# emonTx4-PiZero.net
KiCad netlist of a schematic drawn in EAGLE
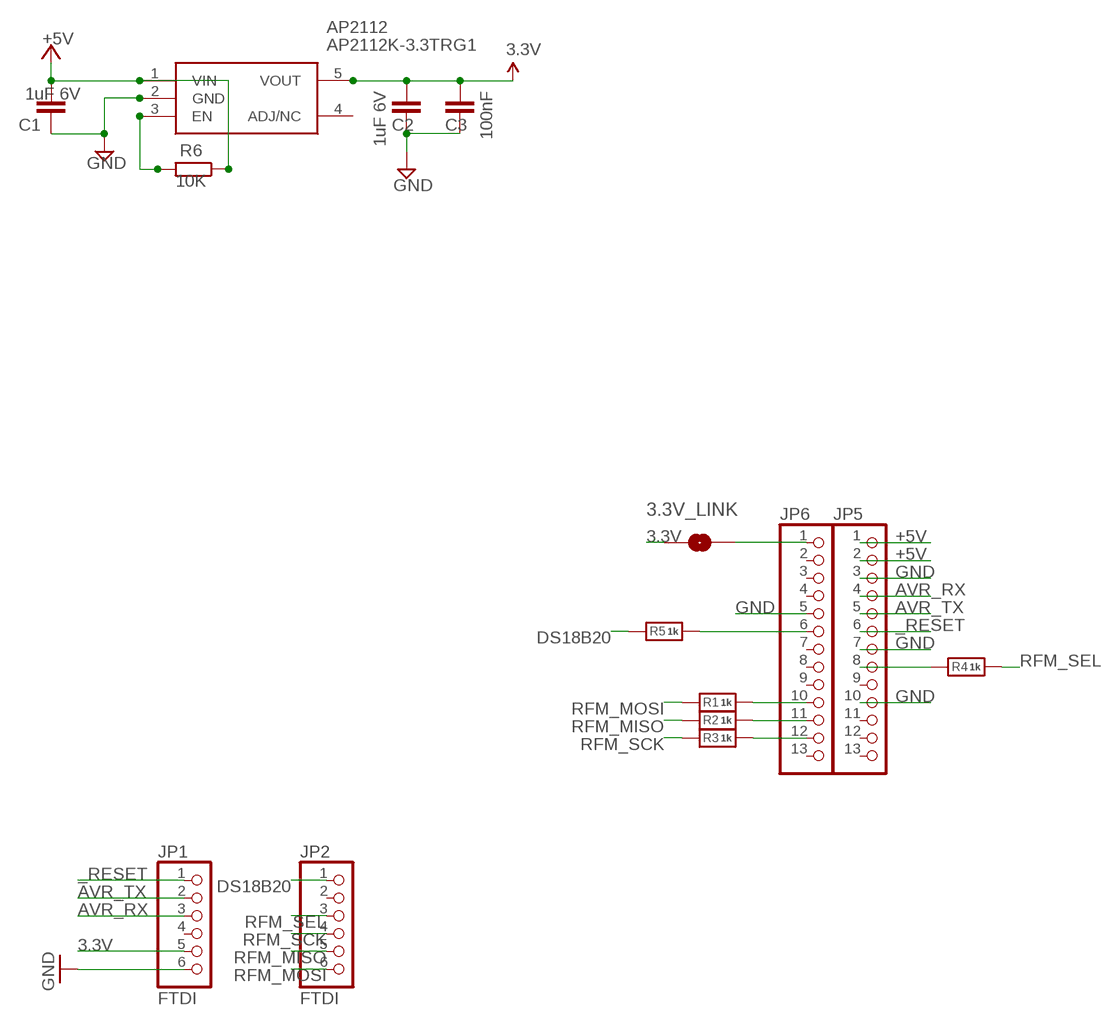
[diagram p0: schematic, sheet 1]

(export (version "E")
  (design (tool "Eeschema 10.0.6"))
  (components
    (comp (ref "3.3V_LINK")
      (value "SOLDERJUMPERNC")
      (footprint "eagle-import:SJ_2S")
      (libsource (lib "eagle-import") (part "SOLDERJUMPERNC"))
    )
    (comp (ref "AP2112")
      (value "AP2112K-3.3TRG1")
      (footprint "eagle-import:SOT95P282X130-5N")
      (fields (field (name "MOUSER_PART_NUMBER") "621-AP2112K-3.3TRG1"))
      (libsource (lib "eagle-import") (part "AP2112K-3.3TRG1"))
    )
    (comp (ref "C1")
      (value "1uF 6V")
      (footprint "eagle-import:C0603")
      (libsource (lib "eagle-import") (part "C-EUC0603"))
    )
    (comp (ref "C2")
      (value "1uF 6V")
      (footprint "eagle-import:C0603")
      (libsource (lib "eagle-import") (part "C-EUC0603"))
    )
    (comp (ref "C3")
      (value "100nF")
      (footprint "eagle-import:C0603")
      (libsource (lib "eagle-import") (part "C-EUC0603"))
    )
    (comp (ref "JP1")
      (value "FTDI")
      (footprint "eagle-import:1X06_ROUND_70")
      (libsource (lib "eagle-import") (part "HEADER-1X670MIL"))
    )
    (comp (ref "JP2")
      (value "FTDI")
      (footprint "eagle-import:1X06_ROUND_70")
      (libsource (lib "eagle-import") (part "HEADER-1X670MIL"))
    )
    (comp (ref "JP5")
      (value "PINHD-1X13_BIG")
      (footprint "eagle-import:1X13-BIG")
      (libsource (lib "eagle-import") (part "PINHD-1X13_BIG"))
    )
    (comp (ref "JP6")
      (value "PINHD-1X13_BIG")
      (footprint "eagle-import:1X13-BIG")
      (libsource (lib "eagle-import") (part "PINHD-1X13_BIG"))
    )
    (comp (ref "R1")
      (value "1k")
      (footprint "eagle-import:_0603")
      (libsource (lib "eagle-import") (part "RESISTOR_0603"))
    )
    (comp (ref "R2")
      (value "1k")
      (footprint "eagle-import:_0603")
      (libsource (lib "eagle-import") (part "RESISTOR_0603"))
    )
    (comp (ref "R3")
      (value "1k")
      (footprint "eagle-import:_0603")
      (libsource (lib "eagle-import") (part "RESISTOR_0603"))
    )
    (comp (ref "R4")
      (value "1k")
      (footprint "eagle-import:_0603")
      (libsource (lib "eagle-import") (part "RESISTOR_0603"))
    )
    (comp (ref "R5")
      (value "1k")
      (footprint "eagle-import:_0603")
      (libsource (lib "eagle-import") (part "RESISTOR_0603"))
    )
    (comp (ref "R6")
      (value "10K")
      (footprint "eagle-import:R0603")
      (libsource (lib "eagle-import") (part "R-EU_R0603"))
    )
  )
  (nets
    (net (code "1") (name "+5V") (class "Default")
      (node (ref "AP2112") (pin "1") (pinfunction "VIN_1") (pintype "bidirectional"))
      (node (ref "C1") (pin "2") (pinfunction "2_2") (pintype "passive"))
      (node (ref "JP5") (pin "1") (pinfunction "1_1") (pintype "passive"))
      (node (ref "JP5") (pin "2") (pinfunction "2_2") (pintype "passive"))
      (node (ref "R6") (pin "1") (pinfunction "1_1") (pintype "passive"))
    )
    (net (code "2") (name "/AVR_RX") (class "Default")
      (node (ref "JP1") (pin "3") (pinfunction "3_3") (pintype "passive"))
      (node (ref "JP5") (pin "4") (pinfunction "4_4") (pintype "passive"))
    )
    (net (code "3") (name "/AVR_TX") (class "Default")
      (node (ref "JP1") (pin "2") (pinfunction "2_2") (pintype "passive"))
      (node (ref "JP5") (pin "5") (pinfunction "5_5") (pintype "passive"))
    )
    (net (code "4") (name "/DS18B20") (class "Default")
      (node (ref "JP2") (pin "1") (pinfunction "1_1") (pintype "passive"))
      (node (ref "R5") (pin "2") (pinfunction "2_2") (pintype "passive"))
    )
    (net (code "5") (name "/RFM_MISO") (class "Default")
      (node (ref "JP2") (pin "5") (pinfunction "5_5") (pintype "passive"))
      (node (ref "R2") (pin "2") (pinfunction "2_2") (pintype "passive"))
    )
    (net (code "6") (name "/RFM_MOSI") (class "Default")
      (node (ref "JP2") (pin "6") (pinfunction "6_6") (pintype "passive"))
      (node (ref "R1") (pin "2") (pinfunction "2_2") (pintype "passive"))
    )
    (net (code "7") (name "/RFM_SCK") (class "Default")
      (node (ref "JP2") (pin "4") (pinfunction "4_4") (pintype "passive"))
      (node (ref "R3") (pin "2") (pinfunction "2_2") (pintype "passive"))
    )
    (net (code "8") (name "/RFM_SEL") (class "Default")
      (node (ref "JP2") (pin "3") (pinfunction "3_3") (pintype "passive"))
      (node (ref "R4") (pin "1") (pinfunction "1_1") (pintype "passive"))
    )
    (net (code "9") (name "/_RESET") (class "Default")
      (node (ref "JP1") (pin "1") (pinfunction "1_1") (pintype "passive"))
      (node (ref "JP5") (pin "6") (pinfunction "6_6") (pintype "passive"))
    )
    (net (code "10") (name "3.3V") (class "Default")
      (node (ref "3.3V_LINK") (pin "1") (pinfunction "1_1") (pintype "passive"))
      (node (ref "AP2112") (pin "5") (pinfunction "VOUT_5") (pintype "bidirectional"))
      (node (ref "C2") (pin "2") (pinfunction "2_2") (pintype "passive"))
      (node (ref "C3") (pin "2") (pinfunction "2_2") (pintype "passive"))
      (node (ref "JP1") (pin "5") (pinfunction "5_5") (pintype "passive"))
    )
    (net (code "11") (name "GND") (class "Default")
      (node (ref "AP2112") (pin "2") (pinfunction "GND_2") (pintype "bidirectional"))
      (node (ref "C1") (pin "1") (pinfunction "1_1") (pintype "passive"))
      (node (ref "C2") (pin "1") (pinfunction "1_1") (pintype "passive"))
      (node (ref "C3") (pin "1") (pinfunction "1_1") (pintype "passive"))
      (node (ref "JP1") (pin "6") (pinfunction "6_6") (pintype "passive"))
      (node (ref "JP5") (pin "10") (pinfunction "10_10") (pintype "passive"))
      (node (ref "JP5") (pin "3") (pinfunction "3_3") (pintype "passive"))
      (node (ref "JP5") (pin "7") (pinfunction "7_7") (pintype "passive"))
      (node (ref "JP6") (pin "5") (pinfunction "5_5") (pintype "passive"))
    )
    (net (code "12") (name "Net-(3.3V_LINK-Pad2)") (class "Default")
      (node (ref "3.3V_LINK") (pin "2") (pinfunction "2_2") (pintype "passive"))
      (node (ref "JP6") (pin "1") (pinfunction "1_1") (pintype "passive"))
    )
    (net (code "13") (name "Net-(AP2112-EN)") (class "Default")
      (node (ref "AP2112") (pin "3") (pinfunction "EN_3") (pintype "bidirectional"))
      (node (ref "R6") (pin "2") (pinfunction "2_2") (pintype "passive"))
    )
    (net (code "14") (name "Net-(JP5-Pad8)") (class "Default")
      (node (ref "JP5") (pin "8") (pinfunction "8_8") (pintype "passive"))
      (node (ref "R4") (pin "2") (pinfunction "2_2") (pintype "passive"))
    )
    (net (code "15") (name "Net-(JP6-Pad6)") (class "Default")
      (node (ref "JP6") (pin "6") (pinfunction "6_6") (pintype "passive"))
      (node (ref "R5") (pin "1") (pinfunction "1_1") (pintype "passive"))
    )
    (net (code "16") (name "Net-(JP6-Pad10)") (class "Default")
      (node (ref "JP6") (pin "10") (pinfunction "10_10") (pintype "passive"))
      (node (ref "R1") (pin "1") (pinfunction "1_1") (pintype "passive"))
    )
    (net (code "17") (name "Net-(JP6-Pad11)") (class "Default")
      (node (ref "JP6") (pin "11") (pinfunction "11_11") (pintype "passive"))
      (node (ref "R2") (pin "1") (pinfunction "1_1") (pintype "passive"))
    )
    (net (code "18") (name "Net-(JP6-Pad12)") (class "Default")
      (node (ref "JP6") (pin "12") (pinfunction "12_12") (pintype "passive"))
      (node (ref "R3") (pin "1") (pinfunction "1_1") (pintype "passive"))
    )
    (net (code "19") (name "unconnected-(AP2112-ADJ{slash}NC-Pad4)") (class "Default")
      (node (ref "AP2112") (pin "4") (pinfunction "ADJ/NC_4") (pintype "bidirectional"))
    )
    (net (code "20") (name "unconnected-(JP1-Pad4)") (class "Default")
      (node (ref "JP1") (pin "4") (pinfunction "4_4") (pintype "passive"))
    )
    (net (code "21") (name "unconnected-(JP2-Pad2)") (class "Default")
      (node (ref "JP2") (pin "2") (pinfunction "2_2") (pintype "passive"))
    )
    (net (code "22") (name "unconnected-(JP5-Pad9)") (class "Default")
      (node (ref "JP5") (pin "9") (pinfunction "9_9") (pintype "passive"))
    )
    (net (code "23") (name "unconnected-(JP5-Pad11)") (class "Default")
      (node (ref "JP5") (pin "11") (pinfunction "11_11") (pintype "passive"))
    )
    (net (code "24") (name "unconnected-(JP5-Pad12)") (class "Default")
      (node (ref "JP5") (pin "12") (pinfunction "12_12") (pintype "passive"))
    )
    (net (code "25") (name "unconnected-(JP5-Pad13)") (class "Default")
      (node (ref "JP5") (pin "13") (pinfunction "13_13") (pintype "passive"))
    )
    (net (code "26") (name "unconnected-(JP6-Pad2)") (class "Default")
      (node (ref "JP6") (pin "2") (pinfunction "2_2") (pintype "passive"))
    )
    (net (code "27") (name "unconnected-(JP6-Pad3)") (class "Default")
      (node (ref "JP6") (pin "3") (pinfunction "3_3") (pintype "passive"))
    )
    (net (code "28") (name "unconnected-(JP6-Pad4)") (class "Default")
      (node (ref "JP6") (pin "4") (pinfunction "4_4") (pintype "passive"))
    )
    (net (code "29") (name "unconnected-(JP6-Pad7)") (class "Default")
      (node (ref "JP6") (pin "7") (pinfunction "7_7") (pintype "passive"))
    )
    (net (code "30") (name "unconnected-(JP6-Pad8)") (class "Default")
      (node (ref "JP6") (pin "8") (pinfunction "8_8") (pintype "passive"))
    )
    (net (code "31") (name "unconnected-(JP6-Pad9)") (class "Default")
      (node (ref "JP6") (pin "9") (pinfunction "9_9") (pintype "passive"))
    )
    (net (code "32") (name "unconnected-(JP6-Pad13)") (class "Default")
      (node (ref "JP6") (pin "13") (pinfunction "13_13") (pintype "passive"))
    )
  )
)
